# Team12.net
KiCad netlist of a schematic drawn in Altium Designer
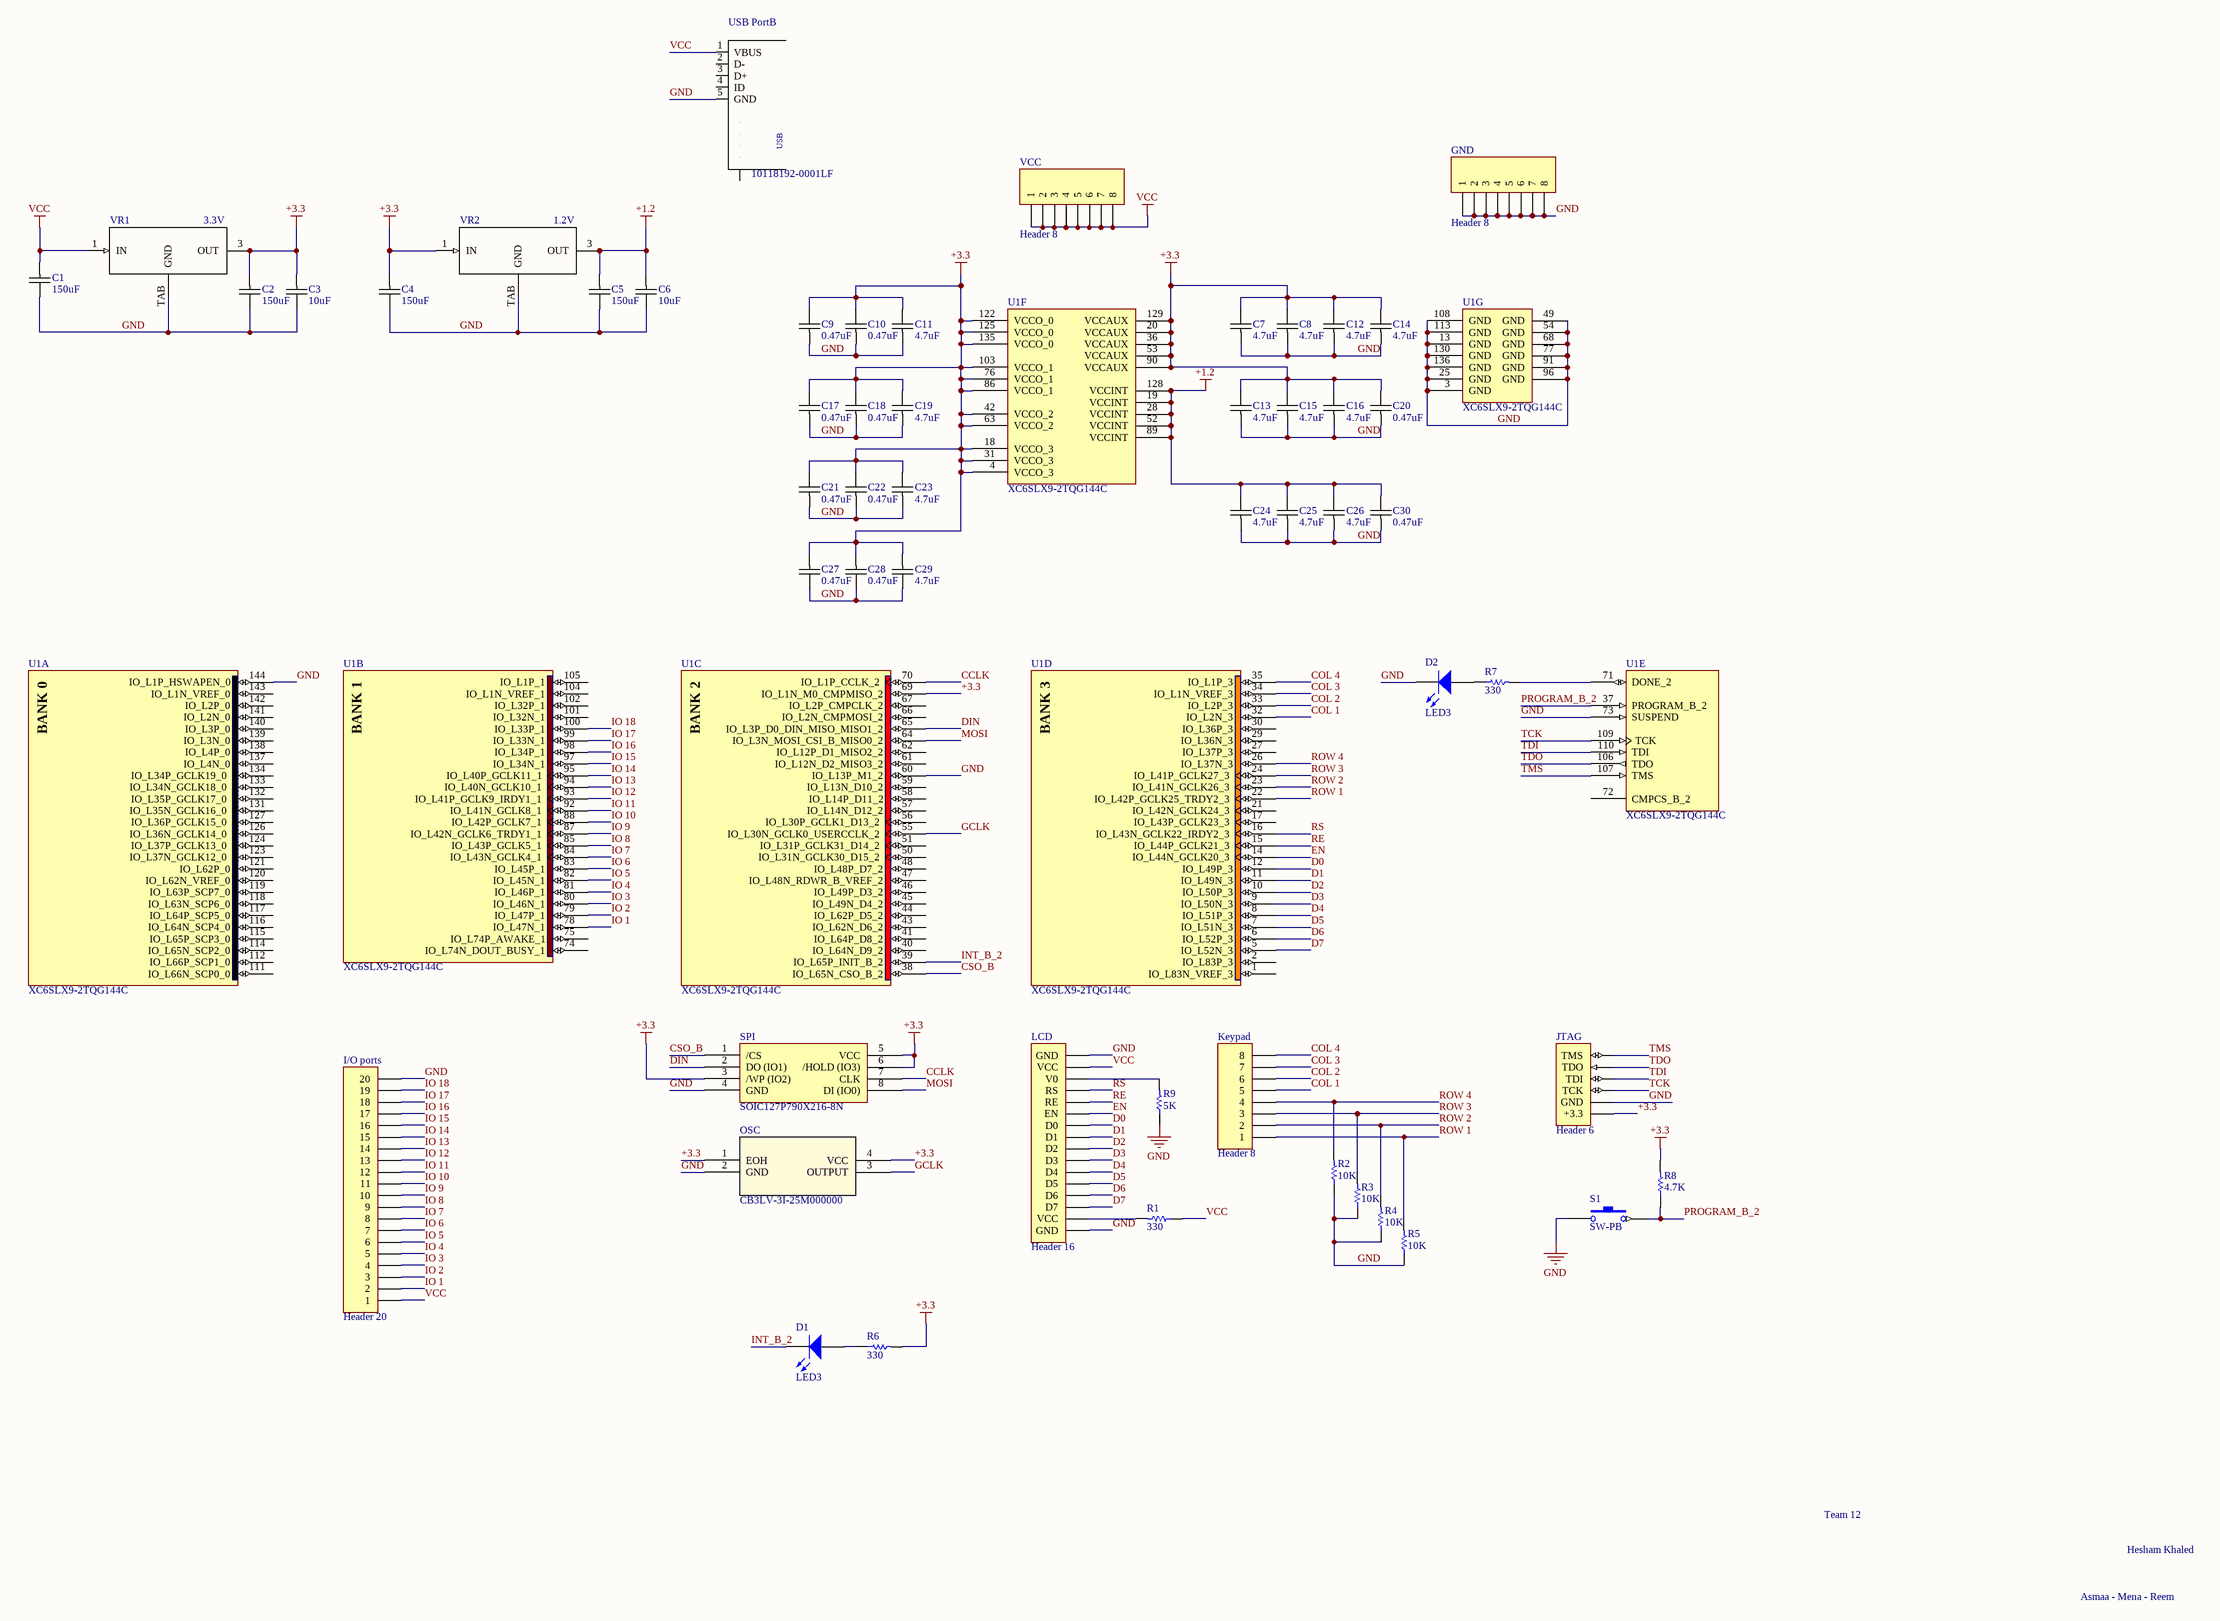
[diagram p0: Team12.SchDoc]

(export (version "E")
  (design (tool "Eeschema 10.0.6"))
  (components
    (comp (ref "C1")
      (value "150uF")
      (footprint "0805C-TBD")
      (description "CAPACITOR 0805 CERAMIC")
      (libsource (lib "vh_altium_library") (part "0805C-27PF-50V-C0G-JOH"))
    )
    (comp (ref "C2")
      (value "150uF")
      (footprint "0805C-TBD")
      (description "CAPACITOR 0805 CERAMIC")
      (libsource (lib "vh_altium_library") (part "0805C-27PF-50V-C0G-JOH"))
    )
    (comp (ref "C3")
      (value "10uF")
      (footprint "0805C-TBD")
      (description "CAPACITOR 0805 CERAMIC")
      (libsource (lib "vh_altium_library") (part "0805C-27PF-50V-C0G-JOH"))
    )
    (comp (ref "C4")
      (value "150uF")
      (footprint "0805C-TBD")
      (description "CAPACITOR 0805 CERAMIC")
      (libsource (lib "vh_altium_library") (part "0805C-27PF-50V-C0G-JOH"))
    )
    (comp (ref "C5")
      (value "150uF")
      (footprint "0805C-TBD")
      (description "CAPACITOR 0805 CERAMIC")
      (libsource (lib "vh_altium_library") (part "0805C-27PF-50V-C0G-JOH"))
    )
    (comp (ref "C6")
      (value "10uF")
      (footprint "0805C-TBD")
      (description "CAPACITOR 0805 CERAMIC")
      (libsource (lib "vh_altium_library") (part "0805C-27PF-50V-C0G-JOH"))
    )
    (comp (ref "C7")
      (value "4.7uF")
      (footprint "0805C-TBD")
      (description "CAPACITOR 0805 CERAMIC")
      (libsource (lib "vh_altium_library") (part "0805C-27PF-50V-C0G-JOH"))
    )
    (comp (ref "C8")
      (value "4.7uF")
      (footprint "0805C-TBD")
      (description "CAPACITOR 0805 CERAMIC")
      (libsource (lib "vh_altium_library") (part "0805C-27PF-50V-C0G-JOH"))
    )
    (comp (ref "C9")
      (value "0.47uF")
      (footprint "0805C-TBD")
      (description "CAPACITOR 0805 CERAMIC")
      (libsource (lib "vh_altium_library") (part "0805C-27PF-50V-C0G-JOH"))
    )
    (comp (ref "C10")
      (value "0.47uF")
      (footprint "0805C-TBD")
      (description "CAPACITOR 0805 CERAMIC")
      (libsource (lib "vh_altium_library") (part "0805C-27PF-50V-C0G-JOH"))
    )
    (comp (ref "C11")
      (value "4.7uF")
      (footprint "0805C-TBD")
      (description "CAPACITOR 0805 CERAMIC")
      (libsource (lib "vh_altium_library") (part "0805C-27PF-50V-C0G-JOH"))
    )
    (comp (ref "C12")
      (value "4.7uF")
      (footprint "0805C-TBD")
      (description "CAPACITOR 0805 CERAMIC")
      (libsource (lib "vh_altium_library") (part "0805C-27PF-50V-C0G-JOH"))
    )
    (comp (ref "C13")
      (value "4.7uF")
      (footprint "0805C-TBD")
      (description "CAPACITOR 0805 CERAMIC")
      (libsource (lib "vh_altium_library") (part "0805C-27PF-50V-C0G-JOH"))
    )
    (comp (ref "C14")
      (value "4.7uF")
      (footprint "0805C-TBD")
      (description "CAPACITOR 0805 CERAMIC")
      (libsource (lib "vh_altium_library") (part "0805C-27PF-50V-C0G-JOH"))
    )
    (comp (ref "C15")
      (value "4.7uF")
      (footprint "0805C-TBD")
      (description "CAPACITOR 0805 CERAMIC")
      (libsource (lib "vh_altium_library") (part "0805C-27PF-50V-C0G-JOH"))
    )
    (comp (ref "C16")
      (value "4.7uF")
      (footprint "0805C-TBD")
      (description "CAPACITOR 0805 CERAMIC")
      (libsource (lib "vh_altium_library") (part "0805C-27PF-50V-C0G-JOH"))
    )
    (comp (ref "C17")
      (value "0.47uF")
      (footprint "0805C-TBD")
      (description "CAPACITOR 0805 CERAMIC")
      (libsource (lib "vh_altium_library") (part "0805C-27PF-50V-C0G-JOH"))
    )
    (comp (ref "C18")
      (value "0.47uF")
      (footprint "0805C-TBD")
      (description "CAPACITOR 0805 CERAMIC")
      (libsource (lib "vh_altium_library") (part "0805C-27PF-50V-C0G-JOH"))
    )
    (comp (ref "C19")
      (value "4.7uF")
      (footprint "0805C-TBD")
      (description "CAPACITOR 0805 CERAMIC")
      (libsource (lib "vh_altium_library") (part "0805C-27PF-50V-C0G-JOH"))
    )
    (comp (ref "C20")
      (value "0.47uF")
      (footprint "0805C-TBD")
      (description "CAPACITOR 0805 CERAMIC")
      (libsource (lib "vh_altium_library") (part "0805C-27PF-50V-C0G-JOH"))
    )
    (comp (ref "C21")
      (value "0.47uF")
      (footprint "0805C-TBD")
      (description "CAPACITOR 0805 CERAMIC")
      (libsource (lib "vh_altium_library") (part "0805C-27PF-50V-C0G-JOH"))
    )
    (comp (ref "C22")
      (value "0.47uF")
      (footprint "0805C-TBD")
      (description "CAPACITOR 0805 CERAMIC")
      (libsource (lib "vh_altium_library") (part "0805C-27PF-50V-C0G-JOH"))
    )
    (comp (ref "C23")
      (value "4.7uF")
      (footprint "0805C-TBD")
      (description "CAPACITOR 0805 CERAMIC")
      (libsource (lib "vh_altium_library") (part "0805C-27PF-50V-C0G-JOH"))
    )
    (comp (ref "C24")
      (value "4.7uF")
      (footprint "0805C-TBD")
      (description "CAPACITOR 0805 CERAMIC")
      (libsource (lib "vh_altium_library") (part "0805C-27PF-50V-C0G-JOH"))
    )
    (comp (ref "C25")
      (value "4.7uF")
      (footprint "0805C-TBD")
      (description "CAPACITOR 0805 CERAMIC")
      (libsource (lib "vh_altium_library") (part "0805C-27PF-50V-C0G-JOH"))
    )
    (comp (ref "C26")
      (value "4.7uF")
      (footprint "0805C-TBD")
      (description "CAPACITOR 0805 CERAMIC")
      (libsource (lib "vh_altium_library") (part "0805C-27PF-50V-C0G-JOH"))
    )
    (comp (ref "C27")
      (value "0.47uF")
      (footprint "0805C-TBD")
      (description "CAPACITOR 0805 CERAMIC")
      (libsource (lib "vh_altium_library") (part "0805C-27PF-50V-C0G-JOH"))
    )
    (comp (ref "C28")
      (value "0.47uF")
      (footprint "0805C-TBD")
      (description "CAPACITOR 0805 CERAMIC")
      (libsource (lib "vh_altium_library") (part "0805C-27PF-50V-C0G-JOH"))
    )
    (comp (ref "C29")
      (value "4.7uF")
      (footprint "0805C-TBD")
      (description "CAPACITOR 0805 CERAMIC")
      (libsource (lib "vh_altium_library") (part "0805C-27PF-50V-C0G-JOH"))
    )
    (comp (ref "C30")
      (value "0.47uF")
      (footprint "0805C-TBD")
      (description "CAPACITOR 0805 CERAMIC")
      (libsource (lib "vh_altium_library") (part "0805C-27PF-50V-C0G-JOH"))
    )
    (comp (ref "D1")
      (value "LED3")
      (footprint "DSO-C2/D5.6")
      (description "Typical BLUE SiC LED")
      (fields (field (name "PUBLISHER") "Altium Limited"))
      (libsource (lib "Miscellaneous Devices") (part "LED3"))
    )
    (comp (ref "D2")
      (value "LED3")
      (footprint "DSO-C2/D5.6")
      (description "Typical BLUE SiC LED")
      (fields (field (name "PUBLISHER") "Altium Limited"))
      (libsource (lib "Miscellaneous Devices") (part "LED3"))
    )
    (comp (ref "GND")
      (value "Header 8")
      (footprint "HDR1X8")
      (description "Header, 8-Pin")
      (fields (field (name "PUBLISHER") "Altium Limited"))
      (libsource (lib "") (part "Header 8_1"))
    )
    (comp (ref "I/O ports")
      (value "Header 20")
      (footprint "HDR1X20")
      (description "Header, 20-Pin")
      (fields (field (name "PUBLISHER") "Altium Limited"))
      (libsource (lib "Miscellaneous Connectors") (part "Header 20"))
    )
    (comp (ref "JTAG")
      (value "Header 6")
      (footprint "HDR1X6")
      (description "Header, 6-Pin")
      (fields (field (name "PUBLISHER") "Altium Limited"))
      (libsource (lib "Miscellaneous Connectors") (part "Header 6"))
    )
    (comp (ref "Keypad")
      (value "Header 8")
      (footprint "HDR1X8")
      (description "Header, 8-Pin")
      (fields (field (name "PUBLISHER") "Altium Limited"))
      (libsource (lib "Miscellaneous Connectors") (part "Header 8"))
    )
    (comp (ref "LCD")
      (value "Header 16")
      (footprint "HDR1X16")
      (description "Header, 16-Pin")
      (fields (field (name "PUBLISHER") "Altium Limited"))
      (libsource (lib "Miscellaneous Connectors") (part "Header 16"))
    )
    (comp (ref "OSC")
      (value "CB3LV-3I-25M000000")
      (footprint "CRYS_CB3LV-3I-01")
      (description "No Description Available")
      (fields
        (field (name "MANUFACTURER_PART_NUMBER") "CB3LV-3I-14M7456")
        (field (name "COPYRIGHT") "Copyright (C) 2018 Accelerated Designs. All rights reserved")
      )
      (libsource (lib "OSC 8MHz CB3LV-3I-25M000000") (part "CB3LV-3I-25M000000"))
    )
    (comp (ref "R1")
      (value "330")
      (footprint "ERA-0805")
      (fields (field (name "PUBLISHER") "Altium Limited"))
      (libsource (lib "Panasonic Resistor") (part "ERA6Y"))
    )
    (comp (ref "R2")
      (value "10K")
      (footprint "ERA-0805")
      (fields (field (name "PUBLISHER") "Altium Limited"))
      (libsource (lib "Panasonic Resistor") (part "ERA6Y"))
    )
    (comp (ref "R3")
      (value "10K")
      (footprint "ERA-0805")
      (fields (field (name "PUBLISHER") "Altium Limited"))
      (libsource (lib "Panasonic Resistor") (part "ERA6Y"))
    )
    (comp (ref "R4")
      (value "10K")
      (footprint "ERA-0805")
      (fields (field (name "PUBLISHER") "Altium Limited"))
      (libsource (lib "Panasonic Resistor") (part "ERA6Y"))
    )
    (comp (ref "R5")
      (value "10K")
      (footprint "ERA-0805")
      (fields (field (name "PUBLISHER") "Altium Limited"))
      (libsource (lib "Panasonic Resistor") (part "ERA6Y"))
    )
    (comp (ref "R6")
      (value "330")
      (footprint "ERA-0805")
      (fields (field (name "PUBLISHER") "Altium Limited"))
      (libsource (lib "Panasonic Resistor") (part "ERA6Y"))
    )
    (comp (ref "R7")
      (value "330")
      (footprint "ERA-0805")
      (fields (field (name "PUBLISHER") "Altium Limited"))
      (libsource (lib "Panasonic Resistor") (part "ERA6Y"))
    )
    (comp (ref "R8")
      (value "4.7K")
      (footprint "ERA-0805")
      (fields (field (name "PUBLISHER") "Altium Limited"))
      (libsource (lib "Panasonic Resistor") (part "ERA6Y"))
    )
    (comp (ref "R9")
      (value "5K")
      (footprint "ERA-0805")
      (fields (field (name "PUBLISHER") "Altium Limited"))
      (libsource (lib "Panasonic Resistor") (part "ERA6Y"))
    )
    (comp (ref "S1")
      (value "SW-PB")
      (footprint "SPST-2")
      (description "Switch")
      (fields (field (name "PUBLISHER") "Altium Limited"))
      (libsource (lib "Miscellaneous Devices") (part "SW-PB"))
    )
    (comp (ref "SPI")
      (value "SOIC127P790X216-8N")
      (footprint "*SOIC127P790X216-8N")
      (description "IC FLASH 8M SPI 104MHZ 8SOIC")
      (libsource (lib "SPI Flash Memory") (part "SOIC127P790X216-8N"))
    )
    (comp (ref "U1")
      (value "XC6SLX9-2TQG144C")
      (footprint "TQG144_N")
      (fields (field (name "PUBLISHER") "Altium Limited"))
      (libsource (lib "Xilinx Spartan-6") (part "XC6SLX9-2TQG144C"))
    )
    (comp (ref "USB PortB")
      (value "10118192-0001LF")
      (footprint "10118192-0001LF_10118192-0001LF(Primary)")
      (description "Conn Micro USB Type B RCP 5 POS 0.65mm Solder RA SMD 5 Terminal 1 Port T/R")
      (fields (field (name "MF") "Amphenol"))
      (libsource (lib "USB Micro Port") (part "10118192-0001LF"))
    )
    (comp (ref "VCC")
      (value "Header 8")
      (footprint "HDR1X8")
      (description "Header, 8-Pin")
      (fields (field (name "PUBLISHER") "Altium Limited"))
      (libsource (lib "") (part "Header 8_1"))
    )
    (comp (ref "VR1")
      (value "3.3V")
      (footprint "*D2PAK_MC7805ACD2TG(Primary)")
      (description "Linear Voltage Regulator IC Positive Fixed 1 Output 1A D2PAK")
      (fields (field (name "MP") "MC7805ACD2TG") (field (name "MF") "ON Semiconductor"))
      (libsource (lib "MC7805ACD2TG") (part "MC7805ACD2TG"))
    )
    (comp (ref "VR2")
      (value "1.2V")
      (footprint "*D2PAK_MC7805ACD2TG(Primary)")
      (description "Linear Voltage Regulator IC Positive Fixed 1 Output 1A D2PAK")
      (fields (field (name "MP") "MC7805ACD2TG") (field (name "MF") "ON Semiconductor"))
      (libsource (lib "MC7805ACD2TG") (part "MC7805ACD2TG"))
    )
  )
  (nets
    (net (code "1") (name "+1.2") (class "Default")
      (node (ref "C24") (pin "2") (pintype "passive"))
      (node (ref "C25") (pin "2") (pintype "passive"))
      (node (ref "C26") (pin "2") (pintype "passive"))
      (node (ref "C30") (pin "2") (pintype "passive"))
      (node (ref "C5") (pin "1") (pintype "passive"))
      (node (ref "C6") (pin "1") (pintype "passive"))
      (node (ref "U1") (pin "128") (pinfunction "VCCINT_128") (pintype "power_in"))
      (node (ref "U1") (pin "19") (pinfunction "VCCINT_19") (pintype "power_in"))
      (node (ref "U1") (pin "28") (pinfunction "VCCINT_28") (pintype "power_in"))
      (node (ref "U1") (pin "52") (pinfunction "VCCINT_52") (pintype "power_in"))
      (node (ref "U1") (pin "89") (pinfunction "VCCINT_89") (pintype "power_in"))
      (node (ref "VR2") (pin "3") (pinfunction "OUT_3") (pintype "power_in"))
    )
    (net (code "2") (name "+3.3") (class "Default")
      (node (ref "C10") (pin "2") (pintype "passive"))
      (node (ref "C11") (pin "2") (pintype "passive"))
      (node (ref "C12") (pin "2") (pintype "passive"))
      (node (ref "C13") (pin "2") (pintype "passive"))
      (node (ref "C14") (pin "2") (pintype "passive"))
      (node (ref "C15") (pin "2") (pintype "passive"))
      (node (ref "C16") (pin "2") (pintype "passive"))
      (node (ref "C17") (pin "2") (pintype "passive"))
      (node (ref "C18") (pin "2") (pintype "passive"))
      (node (ref "C19") (pin "2") (pintype "passive"))
      (node (ref "C2") (pin "1") (pintype "passive"))
      (node (ref "C20") (pin "2") (pintype "passive"))
      (node (ref "C21") (pin "2") (pintype "passive"))
      (node (ref "C22") (pin "2") (pintype "passive"))
      (node (ref "C23") (pin "2") (pintype "passive"))
      (node (ref "C27") (pin "1") (pintype "passive"))
      (node (ref "C28") (pin "1") (pintype "passive"))
      (node (ref "C29") (pin "1") (pintype "passive"))
      (node (ref "C3") (pin "1") (pintype "passive"))
      (node (ref "C4") (pin "1") (pintype "passive"))
      (node (ref "C7") (pin "2") (pintype "passive"))
      (node (ref "C8") (pin "2") (pintype "passive"))
      (node (ref "C9") (pin "2") (pintype "passive"))
      (node (ref "JTAG") (pin "1") (pinfunction "+3.3_1") (pintype "power_in"))
      (node (ref "OSC") (pin "1") (pinfunction "EOH_1") (pintype "passive"))
      (node (ref "OSC") (pin "4") (pinfunction "VCC_4") (pintype "passive"))
      (node (ref "R6") (pin "2") (pinfunction "2_2") (pintype "passive"))
      (node (ref "R8") (pin "2") (pinfunction "2_2") (pintype "passive"))
      (node (ref "SPI") (pin "3") (pinfunction "/WP_(IO2)_3") (pintype "passive"))
      (node (ref "SPI") (pin "5") (pinfunction "VCC_5") (pintype "passive"))
      (node (ref "SPI") (pin "6") (pinfunction "/HOLD_(IO3)_6") (pintype "passive"))
      (node (ref "U1") (pin "103") (pinfunction "VCCO_1_103") (pintype "power_in"))
      (node (ref "U1") (pin "122") (pinfunction "VCCO_0_122") (pintype "power_in"))
      (node (ref "U1") (pin "125") (pinfunction "VCCO_0_125") (pintype "power_in"))
      (node (ref "U1") (pin "129") (pinfunction "VCCAUX_129") (pintype "power_in"))
      (node (ref "U1") (pin "135") (pinfunction "VCCO_0_135") (pintype "power_in"))
      (node (ref "U1") (pin "18") (pinfunction "VCCO_3_18") (pintype "power_in"))
      (node (ref "U1") (pin "20") (pinfunction "VCCAUX_20") (pintype "power_in"))
      (node (ref "U1") (pin "31") (pinfunction "VCCO_3_31") (pintype "power_in"))
      (node (ref "U1") (pin "36") (pinfunction "VCCAUX_36") (pintype "power_in"))
      (node (ref "U1") (pin "4") (pinfunction "VCCO_3_4") (pintype "power_in"))
      (node (ref "U1") (pin "42") (pinfunction "VCCO_2_42") (pintype "power_in"))
      (node (ref "U1") (pin "53") (pinfunction "VCCAUX_53") (pintype "power_in"))
      (node (ref "U1") (pin "63") (pinfunction "VCCO_2_63") (pintype "power_in"))
      (node (ref "U1") (pin "69") (pinfunction "IO_L1N_M0_CMPMISO_2_69") (pintype "bidirectional"))
      (node (ref "U1") (pin "76") (pinfunction "VCCO_1_76") (pintype "power_in"))
      (node (ref "U1") (pin "86") (pinfunction "VCCO_1_86") (pintype "power_in"))
      (node (ref "U1") (pin "90") (pinfunction "VCCAUX_90") (pintype "power_in"))
      (node (ref "VR1") (pin "3") (pinfunction "OUT_3") (pintype "power_in"))
      (node (ref "VR2") (pin "1") (pinfunction "IN_1") (pintype "input"))
    )
    (net (code "3") (name "/CCLK") (class "Default")
      (node (ref "SPI") (pin "7") (pinfunction "CLK_7") (pintype "passive"))
      (node (ref "U1") (pin "70") (pinfunction "IO_L1P_CCLK_2_70") (pintype "bidirectional"))
    )
    (net (code "4") (name "/COL 1") (class "Default")
      (node (ref "Keypad") (pin "5") (pinfunction "5_5") (pintype "passive"))
      (node (ref "U1") (pin "32") (pinfunction "IO_L2N_3_32") (pintype "bidirectional"))
    )
    (net (code "5") (name "/COL 2") (class "Default")
      (node (ref "Keypad") (pin "6") (pinfunction "6_6") (pintype "passive"))
      (node (ref "U1") (pin "33") (pinfunction "IO_L2P_3_33") (pintype "bidirectional"))
    )
    (net (code "6") (name "/COL 3") (class "Default")
      (node (ref "Keypad") (pin "7") (pinfunction "7_7") (pintype "passive"))
      (node (ref "U1") (pin "34") (pinfunction "IO_L1N_VREF_3_34") (pintype "bidirectional"))
    )
    (net (code "7") (name "/COL 4") (class "Default")
      (node (ref "Keypad") (pin "8") (pinfunction "8_8") (pintype "passive"))
      (node (ref "U1") (pin "35") (pinfunction "IO_L1P_3_35") (pintype "bidirectional"))
    )
    (net (code "8") (name "/CSO_B") (class "Default")
      (node (ref "SPI") (pin "1") (pinfunction "/CS_1") (pintype "passive"))
      (node (ref "U1") (pin "38") (pinfunction "IO_L65N_CSO_B_2_38") (pintype "bidirectional"))
    )
    (net (code "9") (name "/D0") (class "Default")
      (node (ref "LCD") (pin "10") (pinfunction "D0_10") (pintype "passive"))
      (node (ref "U1") (pin "12") (pinfunction "IO_L49P_3_12") (pintype "bidirectional"))
    )
    (net (code "10") (name "/D1") (class "Default")
      (node (ref "LCD") (pin "9") (pinfunction "D1_9") (pintype "passive"))
      (node (ref "U1") (pin "11") (pinfunction "IO_L49N_3_11") (pintype "bidirectional"))
    )
    (net (code "11") (name "/D2") (class "Default")
      (node (ref "LCD") (pin "8") (pinfunction "D2_8") (pintype "passive"))
      (node (ref "U1") (pin "10") (pinfunction "IO_L50P_3_10") (pintype "bidirectional"))
    )
    (net (code "12") (name "/D3") (class "Default")
      (node (ref "LCD") (pin "7") (pinfunction "D3_7") (pintype "passive"))
      (node (ref "U1") (pin "9") (pinfunction "IO_L50N_3_9") (pintype "bidirectional"))
    )
    (net (code "13") (name "/D4") (class "Default")
      (node (ref "LCD") (pin "6") (pinfunction "D4_6") (pintype "passive"))
      (node (ref "U1") (pin "8") (pinfunction "IO_L51P_3_8") (pintype "bidirectional"))
    )
    (net (code "14") (name "/D5") (class "Default")
      (node (ref "LCD") (pin "5") (pinfunction "D5_5") (pintype "passive"))
      (node (ref "U1") (pin "7") (pinfunction "IO_L51N_3_7") (pintype "bidirectional"))
    )
    (net (code "15") (name "/D6") (class "Default")
      (node (ref "LCD") (pin "4") (pinfunction "D6_4") (pintype "passive"))
      (node (ref "U1") (pin "6") (pinfunction "IO_L52P_3_6") (pintype "bidirectional"))
    )
    (net (code "16") (name "/D7") (class "Default")
      (node (ref "LCD") (pin "3") (pinfunction "D7_3") (pintype "passive"))
      (node (ref "U1") (pin "5") (pinfunction "IO_L52N_3_5") (pintype "bidirectional"))
    )
    (net (code "17") (name "/DIN") (class "Default")
      (node (ref "SPI") (pin "2") (pinfunction "DO_(IO1)_2") (pintype "passive"))
      (node (ref "U1") (pin "65") (pinfunction "IO_L3P_D0_DIN_MISO_MISO1_2_65") (pintype "bidirectional"))
    )
    (net (code "18") (name "/EN") (class "Default")
      (node (ref "LCD") (pin "11") (pinfunction "EN_11") (pintype "passive"))
      (node (ref "U1") (pin "14") (pinfunction "IO_L44N_GCLK20_3_14") (pintype "bidirectional"))
    )
    (net (code "19") (name "/GCLK") (class "Default")
      (node (ref "OSC") (pin "3") (pinfunction "OUTPUT_3") (pintype "passive"))
      (node (ref "U1") (pin "55") (pinfunction "IO_L30N_GCLK0_USERCCLK_2_55") (pintype "bidirectional"))
    )
    (net (code "20") (name "/INT_B_2") (class "Default")
      (node (ref "D1") (pin "2") (pinfunction "K_2") (pintype "passive"))
      (node (ref "U1") (pin "39") (pinfunction "IO_L65P_INIT_B_2_39") (pintype "bidirectional"))
    )
    (net (code "21") (name "/IO 1") (class "Default")
      (node (ref "I/O ports") (pin "2") (pinfunction "2_2") (pintype "passive"))
      (node (ref "U1") (pin "78") (pinfunction "IO_L47N_1_78") (pintype "bidirectional"))
    )
    (net (code "22") (name "/IO 2") (class "Default")
      (node (ref "I/O ports") (pin "3") (pinfunction "3_3") (pintype "passive"))
      (node (ref "U1") (pin "79") (pinfunction "IO_L47P_1_79") (pintype "bidirectional"))
    )
    (net (code "23") (name "/IO 3") (class "Default")
      (node (ref "I/O ports") (pin "4") (pinfunction "4_4") (pintype "passive"))
      (node (ref "U1") (pin "80") (pinfunction "IO_L46N_1_80") (pintype "bidirectional"))
    )
    (net (code "24") (name "/IO 4") (class "Default")
      (node (ref "I/O ports") (pin "5") (pinfunction "5_5") (pintype "passive"))
      (node (ref "U1") (pin "81") (pinfunction "IO_L46P_1_81") (pintype "bidirectional"))
    )
    (net (code "25") (name "/IO 5") (class "Default")
      (node (ref "I/O ports") (pin "6") (pinfunction "6_6") (pintype "passive"))
      (node (ref "U1") (pin "82") (pinfunction "IO_L45N_1_82") (pintype "bidirectional"))
    )
    (net (code "26") (name "/IO 6") (class "Default")
      (node (ref "I/O ports") (pin "7") (pinfunction "7_7") (pintype "passive"))
      (node (ref "U1") (pin "83") (pinfunction "IO_L45P_1_83") (pintype "bidirectional"))
    )
    (net (code "27") (name "/IO 7") (class "Default")
      (node (ref "I/O ports") (pin "8") (pinfunction "8_8") (pintype "passive"))
      (node (ref "U1") (pin "84") (pinfunction "IO_L43N_GCLK4_1_84") (pintype "bidirectional"))
    )
    (net (code "28") (name "/IO 8") (class "Default")
      (node (ref "I/O ports") (pin "9") (pinfunction "9_9") (pintype "passive"))
      (node (ref "U1") (pin "85") (pinfunction "IO_L43P_GCLK5_1_85") (pintype "bidirectional"))
    )
    (net (code "29") (name "/IO 9") (class "Default")
      (node (ref "I/O ports") (pin "10") (pinfunction "10_10") (pintype "passive"))
      (node (ref "U1") (pin "87") (pinfunction "IO_L42N_GCLK6_TRDY1_1_87") (pintype "bidirectional"))
    )
    (net (code "30") (name "/IO 10") (class "Default")
      (node (ref "I/O ports") (pin "11") (pinfunction "11_11") (pintype "passive"))
      (node (ref "U1") (pin "88") (pinfunction "IO_L42P_GCLK7_1_88") (pintype "bidirectional"))
    )
    (net (code "31") (name "/IO 11") (class "Default")
      (node (ref "I/O ports") (pin "12") (pinfunction "12_12") (pintype "passive"))
      (node (ref "U1") (pin "92") (pinfunction "IO_L41N_GCLK8_1_92") (pintype "bidirectional"))
    )
    (net (code "32") (name "/IO 12") (class "Default")
      (node (ref "I/O ports") (pin "13") (pinfunction "13_13") (pintype "passive"))
      (node (ref "U1") (pin "93") (pinfunction "IO_L41P_GCLK9_IRDY1_1_93") (pintype "bidirectional"))
    )
    (net (code "33") (name "/IO 13") (class "Default")
      (node (ref "I/O ports") (pin "14") (pinfunction "14_14") (pintype "passive"))
      (node (ref "U1") (pin "94") (pinfunction "IO_L40N_GCLK10_1_94") (pintype "bidirectional"))
    )
    (net (code "34") (name "/IO 14") (class "Default")
      (node (ref "I/O ports") (pin "15") (pinfunction "15_15") (pintype "passive"))
      (node (ref "U1") (pin "95") (pinfunction "IO_L40P_GCLK11_1_95") (pintype "bidirectional"))
    )
    (net (code "35") (name "/IO 15") (class "Default")
      (node (ref "I/O ports") (pin "16") (pinfunction "16_16") (pintype "passive"))
      (node (ref "U1") (pin "97") (pinfunction "IO_L34N_1_97") (pintype "bidirectional"))
    )
    (net (code "36") (name "/IO 16") (class "Default")
      (node (ref "I/O ports") (pin "17") (pinfunction "17_17") (pintype "passive"))
      (node (ref "U1") (pin "98") (pinfunction "IO_L34P_1_98") (pintype "bidirectional"))
    )
    (net (code "37") (name "/IO 17") (class "Default")
      (node (ref "I/O ports") (pin "18") (pinfunction "18_18") (pintype "passive"))
      (node (ref "U1") (pin "99") (pinfunction "IO_L33N_1_99") (pintype "bidirectional"))
    )
    (net (code "38") (name "/IO 18") (class "Default")
      (node (ref "I/O ports") (pin "19") (pinfunction "19_19") (pintype "passive"))
      (node (ref "U1") (pin "100") (pinfunction "IO_L33P_1_100") (pintype "bidirectional"))
    )
    (net (code "39") (name "/MOSI") (class "Default")
      (node (ref "SPI") (pin "8") (pinfunction "DI_(IO0)_8") (pintype "passive"))
      (node (ref "U1") (pin "64") (pinfunction "IO_L3N_MOSI_CSI_B_MISO0_2_64") (pintype "bidirectional"))
    )
    (net (code "40") (name "/PROGRAM_B_2") (class "Default")
      (node (ref "R8") (pin "1") (pinfunction "1_1") (pintype "passive"))
      (node (ref "S1") (pin "2") (pinfunction "2_2") (pintype "output"))
      (node (ref "U1") (pin "37") (pinfunction "PROGRAM_B_2_37") (pintype "input"))
    )
    (net (code "41") (name "/RE") (class "Default")
      (node (ref "LCD") (pin "12") (pinfunction "RE_12") (pintype "passive"))
      (node (ref "U1") (pin "15") (pinfunction "IO_L44P_GCLK21_3_15") (pintype "bidirectional"))
    )
    (net (code "42") (name "/ROW 1") (class "Default")
      (node (ref "Keypad") (pin "1") (pinfunction "1_1") (pintype "passive"))
      (node (ref "R5") (pin "2") (pinfunction "2_2") (pintype "passive"))
      (node (ref "U1") (pin "22") (pinfunction "IO_L42P_GCLK25_TRDY2_3_22") (pintype "bidirectional"))
    )
    (net (code "43") (name "/ROW 2") (class "Default")
      (node (ref "Keypad") (pin "2") (pinfunction "2_2") (pintype "passive"))
      (node (ref "R4") (pin "2") (pinfunction "2_2") (pintype "passive"))
      (node (ref "U1") (pin "23") (pinfunction "IO_L41N_GCLK26_3_23") (pintype "bidirectional"))
    )
    (net (code "44") (name "/ROW 3") (class "Default")
      (node (ref "Keypad") (pin "3") (pinfunction "3_3") (pintype "passive"))
      (node (ref "R3") (pin "2") (pinfunction "2_2") (pintype "passive"))
      (node (ref "U1") (pin "24") (pinfunction "IO_L41P_GCLK27_3_24") (pintype "bidirectional"))
    )
    (net (code "45") (name "/ROW 4") (class "Default")
      (node (ref "Keypad") (pin "4") (pinfunction "4_4") (pintype "passive"))
      (node (ref "R2") (pin "2") (pinfunction "2_2") (pintype "passive"))
      (node (ref "U1") (pin "26") (pinfunction "IO_L37N_3_26") (pintype "bidirectional"))
    )
    (net (code "46") (name "/RS") (class "Default")
      (node (ref "LCD") (pin "13") (pinfunction "RS_13") (pintype "passive"))
      (node (ref "U1") (pin "16") (pinfunction "IO_L43N_GCLK22_IRDY2_3_16") (pintype "bidirectional"))
    )
    (net (code "47") (name "/TCK") (class "Default")
      (node (ref "JTAG") (pin "3") (pinfunction "TCK_3") (pintype "bidirectional"))
      (node (ref "U1") (pin "109") (pinfunction "TCK_109") (pintype "input"))
    )
    (net (code "48") (name "/TDI") (class "Default")
      (node (ref "JTAG") (pin "4") (pinfunction "TDI_4") (pintype "bidirectional"))
      (node (ref "U1") (pin "110") (pinfunction "TDI_110") (pintype "input"))
    )
    (net (code "49") (name "/TDO") (class "Default")
      (node (ref "JTAG") (pin "5") (pinfunction "TDO_5") (pintype "input"))
      (node (ref "U1") (pin "106") (pinfunction "TDO_106") (pintype "output"))
    )
    (net (code "50") (name "/TMS") (class "Default")
      (node (ref "JTAG") (pin "6") (pinfunction "TMS_6") (pintype "bidirectional"))
      (node (ref "U1") (pin "107") (pinfunction "TMS_107") (pintype "input"))
    )
    (net (code "51") (name "GND") (class "Default")
      (node (ref "C1") (pin "2") (pintype "passive"))
      (node (ref "C10") (pin "1") (pintype "passive"))
      (node (ref "C11") (pin "1") (pintype "passive"))
      (node (ref "C12") (pin "1") (pintype "passive"))
      (node (ref "C13") (pin "1") (pintype "passive"))
      (node (ref "C14") (pin "1") (pintype "passive"))
      (node (ref "C15") (pin "1") (pintype "passive"))
      (node (ref "C16") (pin "1") (pintype "passive"))
      (node (ref "C17") (pin "1") (pintype "passive"))
      (node (ref "C18") (pin "1") (pintype "passive"))
      (node (ref "C19") (pin "1") (pintype "passive"))
      (node (ref "C2") (pin "2") (pintype "passive"))
      (node (ref "C20") (pin "1") (pintype "passive"))
      (node (ref "C21") (pin "1") (pintype "passive"))
      (node (ref "C22") (pin "1") (pintype "passive"))
      (node (ref "C23") (pin "1") (pintype "passive"))
      (node (ref "C24") (pin "1") (pintype "passive"))
      (node (ref "C25") (pin "1") (pintype "passive"))
      (node (ref "C26") (pin "1") (pintype "passive"))
      (node (ref "C27") (pin "2") (pintype "passive"))
      (node (ref "C28") (pin "2") (pintype "passive"))
      (node (ref "C29") (pin "2") (pintype "passive"))
      (node (ref "C3") (pin "2") (pintype "passive"))
      (node (ref "C30") (pin "1") (pintype "passive"))
      (node (ref "C4") (pin "2") (pintype "passive"))
      (node (ref "C5") (pin "2") (pintype "passive"))
      (node (ref "C6") (pin "2") (pintype "passive"))
      (node (ref "C7") (pin "1") (pintype "passive"))
      (node (ref "C8") (pin "1") (pintype "passive"))
      (node (ref "C9") (pin "1") (pintype "passive"))
      (node (ref "D2") (pin "2") (pinfunction "K_2") (pintype "passive"))
      (node (ref "GND") (pin "1") (pinfunction "1_1") (pintype "passive"))
      (node (ref "GND") (pin "2") (pinfunction "2_2") (pintype "passive"))
      (node (ref "GND") (pin "3") (pinfunction "3_3") (pintype "passive"))
      (node (ref "GND") (pin "4") (pinfunction "4_4") (pintype "passive"))
      (node (ref "GND") (pin "5") (pinfunction "5_5") (pintype "passive"))
      (node (ref "GND") (pin "6") (pinfunction "6_6") (pintype "passive"))
      (node (ref "GND") (pin "7") (pinfunction "7_7") (pintype "passive"))
      (node (ref "GND") (pin "8") (pinfunction "8_8") (pintype "passive"))
      (node (ref "I/O ports") (pin "20") (pinfunction "20_20") (pintype "passive"))
      (node (ref "JTAG") (pin "2") (pinfunction "GND_2") (pintype "power_in"))
      (node (ref "LCD") (pin "1") (pinfunction "GND_1") (pintype "power_in"))
      (node (ref "LCD") (pin "16") (pinfunction "GND_16") (pintype "power_in"))
      (node (ref "OSC") (pin "2") (pinfunction "GND_2") (pintype "passive"))
      (node (ref "R2") (pin "1") (pinfunction "1_1") (pintype "passive"))
      (node (ref "R3") (pin "1") (pinfunction "1_1") (pintype "passive"))
      (node (ref "R4") (pin "1") (pinfunction "1_1") (pintype "passive"))
      (node (ref "R5") (pin "1") (pinfunction "1_1") (pintype "passive"))
      (node (ref "R9") (pin "1") (pinfunction "1_1") (pintype "passive"))
      (node (ref "S1") (pin "1") (pinfunction "GND_1") (pintype "power_in"))
      (node (ref "SPI") (pin "4") (pinfunction "GND_4") (pintype "passive"))
      (node (ref "U1") (pin "108") (pinfunction "GND_108") (pintype "power_in"))
      (node (ref "U1") (pin "113") (pinfunction "GND_113") (pintype "power_in"))
      (node (ref "U1") (pin "13") (pinfunction "GND_13") (pintype "power_in"))
      (node (ref "U1") (pin "130") (pinfunction "GND_130") (pintype "power_in"))
      (node (ref "U1") (pin "136") (pinfunction "GND_136") (pintype "power_in"))
      (node (ref "U1") (pin "144") (pinfunction "IO_L1P_HSWAPEN_0_144") (pintype "bidirectional"))
      (node (ref "U1") (pin "25") (pinfunction "GND_25") (pintype "power_in"))
      (node (ref "U1") (pin "3") (pinfunction "GND_3") (pintype "power_in"))
      (node (ref "U1") (pin "49") (pinfunction "GND_49") (pintype "power_in"))
      (node (ref "U1") (pin "54") (pinfunction "GND_54") (pintype "power_in"))
      (node (ref "U1") (pin "60") (pinfunction "IO_L13P_M1_2_60") (pintype "bidirectional"))
      (node (ref "U1") (pin "68") (pinfunction "GND_68") (pintype "power_in"))
      (node (ref "U1") (pin "73") (pinfunction "SUSPEND_73") (pintype "input"))
      (node (ref "U1") (pin "77") (pinfunction "GND_77") (pintype "power_in"))
      (node (ref "U1") (pin "91") (pinfunction "GND_91") (pintype "power_in"))
      (node (ref "U1") (pin "96") (pinfunction "GND_96") (pintype "power_in"))
      (node (ref "USB PortB") (pin "5") (pinfunction "GND_5") (pintype "power_in"))
      (node (ref "VR1") (pin "TAB") (pinfunction "GND_TAB") (pintype "power_in"))
      (node (ref "VR2") (pin "TAB") (pinfunction "GND_TAB") (pintype "power_in"))
    )
    (net (code "52") (name "Net-(D1-A)") (class "Default")
      (node (ref "D1") (pin "1") (pinfunction "A_1") (pintype "passive"))
      (node (ref "R6") (pin "1") (pinfunction "1_1") (pintype "passive"))
    )
    (net (code "53") (name "Net-(D2-A)") (class "Default")
      (node (ref "D2") (pin "1") (pinfunction "A_1") (pintype "passive"))
      (node (ref "R7") (pin "1") (pinfunction "1_1") (pintype "passive"))
    )
    (net (code "54") (name "Net-(LCD-V0)") (class "Default")
      (node (ref "LCD") (pin "14") (pinfunction "V0_14") (pintype "passive"))
      (node (ref "R9") (pin "2") (pinfunction "2_2") (pintype "passive"))
    )
    (net (code "55") (name "Net-(LCD-VCC-Pad2)") (class "Default")
      (node (ref "LCD") (pin "2") (pinfunction "VCC_2") (pintype "power_in"))
      (node (ref "R1") (pin "2") (pinfunction "2_2") (pintype "passive"))
    )
    (net (code "56") (name "Net-(U1E-DONE_2)") (class "Default")
      (node (ref "R7") (pin "2") (pinfunction "2_2") (pintype "passive"))
      (node (ref "U1") (pin "71") (pinfunction "DONE_2_71") (pintype "bidirectional"))
    )
    (net (code "57") (name "VCC") (class "Default")
      (node (ref "C1") (pin "1") (pintype "passive"))
      (node (ref "I/O ports") (pin "1") (pinfunction "1_1") (pintype "passive"))
      (node (ref "LCD") (pin "15") (pinfunction "VCC_15") (pintype "power_in"))
      (node (ref "R1") (pin "1") (pinfunction "1_1") (pintype "passive"))
      (node (ref "USB PortB") (pin "1") (pinfunction "VBUS_1") (pintype "power_in"))
      (node (ref "VCC") (pin "1") (pinfunction "1_1") (pintype "passive"))
      (node (ref "VCC") (pin "2") (pinfunction "2_2") (pintype "passive"))
      (node (ref "VCC") (pin "3") (pinfunction "3_3") (pintype "passive"))
      (node (ref "VCC") (pin "4") (pinfunction "4_4") (pintype "passive"))
      (node (ref "VCC") (pin "5") (pinfunction "5_5") (pintype "passive"))
      (node (ref "VCC") (pin "6") (pinfunction "6_6") (pintype "passive"))
      (node (ref "VCC") (pin "7") (pinfunction "7_7") (pintype "passive"))
      (node (ref "VCC") (pin "8") (pinfunction "8_8") (pintype "passive"))
      (node (ref "VR1") (pin "1") (pinfunction "IN_1") (pintype "input"))
    )
    (net (code "58") (name "unconnected-(U1A-IO_L1N_VREF_0-Pad143)") (class "Default")
      (node (ref "U1") (pin "143") (pinfunction "IO_L1N_VREF_0_143") (pintype "bidirectional"))
    )
    (net (code "59") (name "unconnected-(U1A-IO_L2N_0-Pad141)") (class "Default")
      (node (ref "U1") (pin "141") (pinfunction "IO_L2N_0_141") (pintype "bidirectional"))
    )
    (net (code "60") (name "unconnected-(U1A-IO_L2P_0-Pad142)") (class "Default")
      (node (ref "U1") (pin "142") (pinfunction "IO_L2P_0_142") (pintype "bidirectional"))
    )
    (net (code "61") (name "unconnected-(U1A-IO_L3N_0-Pad139)") (class "Default")
      (node (ref "U1") (pin "139") (pinfunction "IO_L3N_0_139") (pintype "bidirectional"))
    )
    (net (code "62") (name "unconnected-(U1A-IO_L3P_0-Pad140)") (class "Default")
      (node (ref "U1") (pin "140") (pinfunction "IO_L3P_0_140") (pintype "bidirectional"))
    )
    (net (code "63") (name "unconnected-(U1A-IO_L4N_0-Pad137)") (class "Default")
      (node (ref "U1") (pin "137") (pinfunction "IO_L4N_0_137") (pintype "bidirectional"))
    )
    (net (code "64") (name "unconnected-(U1A-IO_L4P_0-Pad138)") (class "Default")
      (node (ref "U1") (pin "138") (pinfunction "IO_L4P_0_138") (pintype "bidirectional"))
    )
    (net (code "65") (name "unconnected-(U1A-IO_L34N_GCLK18_0-Pad133)") (class "Default")
      (node (ref "U1") (pin "133") (pinfunction "IO_L34N_GCLK18_0_133") (pintype "bidirectional"))
    )
    (net (code "66") (name "unconnected-(U1A-IO_L34P_GCLK19_0-Pad134)") (class "Default")
      (node (ref "U1") (pin "134") (pinfunction "IO_L34P_GCLK19_0_134") (pintype "bidirectional"))
    )
    (net (code "67") (name "unconnected-(U1A-IO_L35N_GCLK16_0-Pad131)") (class "Default")
      (node (ref "U1") (pin "131") (pinfunction "IO_L35N_GCLK16_0_131") (pintype "bidirectional"))
    )
    (net (code "68") (name "unconnected-(U1A-IO_L35P_GCLK17_0-Pad132)") (class "Default")
      (node (ref "U1") (pin "132") (pinfunction "IO_L35P_GCLK17_0_132") (pintype "bidirectional"))
    )
    (net (code "69") (name "unconnected-(U1A-IO_L36N_GCLK14_0-Pad126)") (class "Default")
      (node (ref "U1") (pin "126") (pinfunction "IO_L36N_GCLK14_0_126") (pintype "bidirectional"))
    )
    (net (code "70") (name "unconnected-(U1A-IO_L36P_GCLK15_0-Pad127)") (class "Default")
      (node (ref "U1") (pin "127") (pinfunction "IO_L36P_GCLK15_0_127") (pintype "bidirectional"))
    )
    (net (code "71") (name "unconnected-(U1A-IO_L37N_GCLK12_0-Pad123)") (class "Default")
      (node (ref "U1") (pin "123") (pinfunction "IO_L37N_GCLK12_0_123") (pintype "bidirectional"))
    )
    (net (code "72") (name "unconnected-(U1A-IO_L37P_GCLK13_0-Pad124)") (class "Default")
      (node (ref "U1") (pin "124") (pinfunction "IO_L37P_GCLK13_0_124") (pintype "bidirectional"))
    )
    (net (code "73") (name "unconnected-(U1A-IO_L62N_VREF_0-Pad120)") (class "Default")
      (node (ref "U1") (pin "120") (pinfunction "IO_L62N_VREF_0_120") (pintype "bidirectional"))
    )
    (net (code "74") (name "unconnected-(U1A-IO_L62P_0-Pad121)") (class "Default")
      (node (ref "U1") (pin "121") (pinfunction "IO_L62P_0_121") (pintype "bidirectional"))
    )
    (net (code "75") (name "unconnected-(U1A-IO_L63N_SCP6_0-Pad118)") (class "Default")
      (node (ref "U1") (pin "118") (pinfunction "IO_L63N_SCP6_0_118") (pintype "bidirectional"))
    )
    (net (code "76") (name "unconnected-(U1A-IO_L63P_SCP7_0-Pad119)") (class "Default")
      (node (ref "U1") (pin "119") (pinfunction "IO_L63P_SCP7_0_119") (pintype "bidirectional"))
    )
    (net (code "77") (name "unconnected-(U1A-IO_L64N_SCP4_0-Pad116)") (class "Default")
      (node (ref "U1") (pin "116") (pinfunction "IO_L64N_SCP4_0_116") (pintype "bidirectional"))
    )
    (net (code "78") (name "unconnected-(U1A-IO_L64P_SCP5_0-Pad117)") (class "Default")
      (node (ref "U1") (pin "117") (pinfunction "IO_L64P_SCP5_0_117") (pintype "bidirectional"))
    )
    (net (code "79") (name "unconnected-(U1A-IO_L65N_SCP2_0-Pad114)") (class "Default")
      (node (ref "U1") (pin "114") (pinfunction "IO_L65N_SCP2_0_114") (pintype "bidirectional"))
    )
    (net (code "80") (name "unconnected-(U1A-IO_L65P_SCP3_0-Pad115)") (class "Default")
      (node (ref "U1") (pin "115") (pinfunction "IO_L65P_SCP3_0_115") (pintype "bidirectional"))
    )
    (net (code "81") (name "unconnected-(U1A-IO_L66N_SCP0_0-Pad111)") (class "Default")
      (node (ref "U1") (pin "111") (pinfunction "IO_L66N_SCP0_0_111") (pintype "bidirectional"))
    )
    (net (code "82") (name "unconnected-(U1A-IO_L66P_SCP1_0-Pad112)") (class "Default")
      (node (ref "U1") (pin "112") (pinfunction "IO_L66P_SCP1_0_112") (pintype "bidirectional"))
    )
    (net (code "83") (name "unconnected-(U1B-IO_L1N_VREF_1-Pad104)") (class "Default")
      (node (ref "U1") (pin "104") (pinfunction "IO_L1N_VREF_1_104") (pintype "bidirectional"))
    )
    (net (code "84") (name "unconnected-(U1B-IO_L1P_1-Pad105)") (class "Default")
      (node (ref "U1") (pin "105") (pinfunction "IO_L1P_1_105") (pintype "bidirectional"))
    )
    (net (code "85") (name "unconnected-(U1B-IO_L32N_1-Pad101)") (class "Default")
      (node (ref "U1") (pin "101") (pinfunction "IO_L32N_1_101") (pintype "bidirectional"))
    )
    (net (code "86") (name "unconnected-(U1B-IO_L32P_1-Pad102)") (class "Default")
      (node (ref "U1") (pin "102") (pinfunction "IO_L32P_1_102") (pintype "bidirectional"))
    )
    (net (code "87") (name "unconnected-(U1B-IO_L74N_DOUT_BUSY_1-Pad74)") (class "Default")
      (node (ref "U1") (pin "74") (pinfunction "IO_L74N_DOUT_BUSY_1_74") (pintype "bidirectional"))
    )
    (net (code "88") (name "unconnected-(U1B-IO_L74P_AWAKE_1-Pad75)") (class "Default")
      (node (ref "U1") (pin "75") (pinfunction "IO_L74P_AWAKE_1_75") (pintype "bidirectional"))
    )
    (net (code "89") (name "unconnected-(U1C-IO_L2N_CMPMOSI_2-Pad66)") (class "Default")
      (node (ref "U1") (pin "66") (pinfunction "IO_L2N_CMPMOSI_2_66") (pintype "bidirectional"))
    )
    (net (code "90") (name "unconnected-(U1C-IO_L2P_CMPCLK_2-Pad67)") (class "Default")
      (node (ref "U1") (pin "67") (pinfunction "IO_L2P_CMPCLK_2_67") (pintype "bidirectional"))
    )
    (net (code "91") (name "unconnected-(U1C-IO_L12N_D2_MISO3_2-Pad61)") (class "Default")
      (node (ref "U1") (pin "61") (pinfunction "IO_L12N_D2_MISO3_2_61") (pintype "bidirectional"))
    )
    (net (code "92") (name "unconnected-(U1C-IO_L12P_D1_MISO2_2-Pad62)") (class "Default")
      (node (ref "U1") (pin "62") (pinfunction "IO_L12P_D1_MISO2_2_62") (pintype "bidirectional"))
    )
    (net (code "93") (name "unconnected-(U1C-IO_L13N_D10_2-Pad59)") (class "Default")
      (node (ref "U1") (pin "59") (pinfunction "IO_L13N_D10_2_59") (pintype "bidirectional"))
    )
    (net (code "94") (name "unconnected-(U1C-IO_L14N_D12_2-Pad57)") (class "Default")
      (node (ref "U1") (pin "57") (pinfunction "IO_L14N_D12_2_57") (pintype "bidirectional"))
    )
    (net (code "95") (name "unconnected-(U1C-IO_L14P_D11_2-Pad58)") (class "Default")
      (node (ref "U1") (pin "58") (pinfunction "IO_L14P_D11_2_58") (pintype "bidirectional"))
    )
    (net (code "96") (name "unconnected-(U1C-IO_L30P_GCLK1_D13_2-Pad56)") (class "Default")
      (node (ref "U1") (pin "56") (pinfunction "IO_L30P_GCLK1_D13_2_56") (pintype "bidirectional"))
    )
    (net (code "97") (name "unconnected-(U1C-IO_L31N_GCLK30_D15_2-Pad50)") (class "Default")
      (node (ref "U1") (pin "50") (pinfunction "IO_L31N_GCLK30_D15_2_50") (pintype "bidirectional"))
    )
    (net (code "98") (name "unconnected-(U1C-IO_L31P_GCLK31_D14_2-Pad51)") (class "Default")
      (node (ref "U1") (pin "51") (pinfunction "IO_L31P_GCLK31_D14_2_51") (pintype "bidirectional"))
    )
    (net (code "99") (name "unconnected-(U1C-IO_L48N_RDWR_B_VREF_2-Pad47)") (class "Default")
      (node (ref "U1") (pin "47") (pinfunction "IO_L48N_RDWR_B_VREF_2_47") (pintype "bidirectional"))
    )
    (net (code "100") (name "unconnected-(U1C-IO_L48P_D7_2-Pad48)") (class "Default")
      (node (ref "U1") (pin "48") (pinfunction "IO_L48P_D7_2_48") (pintype "bidirectional"))
    )
    (net (code "101") (name "unconnected-(U1C-IO_L49N_D4_2-Pad45)") (class "Default")
      (node (ref "U1") (pin "45") (pinfunction "IO_L49N_D4_2_45") (pintype "bidirectional"))
    )
    (net (code "102") (name "unconnected-(U1C-IO_L49P_D3_2-Pad46)") (class "Default")
      (node (ref "U1") (pin "46") (pinfunction "IO_L49P_D3_2_46") (pintype "bidirectional"))
    )
    (net (code "103") (name "unconnected-(U1C-IO_L62N_D6_2-Pad43)") (class "Default")
      (node (ref "U1") (pin "43") (pinfunction "IO_L62N_D6_2_43") (pintype "bidirectional"))
    )
    (net (code "104") (name "unconnected-(U1C-IO_L62P_D5_2-Pad44)") (class "Default")
      (node (ref "U1") (pin "44") (pinfunction "IO_L62P_D5_2_44") (pintype "bidirectional"))
    )
    (net (code "105") (name "unconnected-(U1C-IO_L64N_D9_2-Pad40)") (class "Default")
      (node (ref "U1") (pin "40") (pinfunction "IO_L64N_D9_2_40") (pintype "bidirectional"))
    )
    (net (code "106") (name "unconnected-(U1C-IO_L64P_D8_2-Pad41)") (class "Default")
      (node (ref "U1") (pin "41") (pinfunction "IO_L64P_D8_2_41") (pintype "bidirectional"))
    )
    (net (code "107") (name "unconnected-(U1D-IO_L36N_3-Pad29)") (class "Default")
      (node (ref "U1") (pin "29") (pinfunction "IO_L36N_3_29") (pintype "bidirectional"))
    )
    (net (code "108") (name "unconnected-(U1D-IO_L36P_3-Pad30)") (class "Default")
      (node (ref "U1") (pin "30") (pinfunction "IO_L36P_3_30") (pintype "bidirectional"))
    )
    (net (code "109") (name "unconnected-(U1D-IO_L37P_3-Pad27)") (class "Default")
      (node (ref "U1") (pin "27") (pinfunction "IO_L37P_3_27") (pintype "bidirectional"))
    )
    (net (code "110") (name "unconnected-(U1D-IO_L42N_GCLK24_3-Pad21)") (class "Default")
      (node (ref "U1") (pin "21") (pinfunction "IO_L42N_GCLK24_3_21") (pintype "bidirectional"))
    )
    (net (code "111") (name "unconnected-(U1D-IO_L43P_GCLK23_3-Pad17)") (class "Default")
      (node (ref "U1") (pin "17") (pinfunction "IO_L43P_GCLK23_3_17") (pintype "bidirectional"))
    )
    (net (code "112") (name "unconnected-(U1D-IO_L83N_VREF_3-Pad1)") (class "Default")
      (node (ref "U1") (pin "1") (pinfunction "IO_L83N_VREF_3_1") (pintype "bidirectional"))
    )
    (net (code "113") (name "unconnected-(U1D-IO_L83P_3-Pad2)") (class "Default")
      (node (ref "U1") (pin "2") (pinfunction "IO_L83P_3_2") (pintype "bidirectional"))
    )
    (net (code "114") (name "unconnected-(U1E-CMPCS_B_2-Pad72)") (class "Default")
      (node (ref "U1") (pin "72") (pinfunction "CMPCS_B_2_72") (pintype "input"))
    )
    (net (code "115") (name "unconnected-(USB PortB-D+-Pad3)") (class "Default")
      (node (ref "USB PortB") (pin "3") (pinfunction "D+_3") (pintype "passive"))
    )
    (net (code "116") (name "unconnected-(USB PortB-D--Pad2)") (class "Default")
      (node (ref "USB PortB") (pin "2") (pinfunction "D-_2") (pintype "passive"))
    )
    (net (code "117") (name "unconnected-(USB PortB-ID-Pad4)") (class "Default")
      (node (ref "USB PortB") (pin "4") (pinfunction "ID_4") (pintype "passive"))
    )
    (net (code "118") (name "unconnected-(USB PortB-S-PadM1)") (class "Default")
      (node (ref "USB PortB") (pin "M1") (pinfunction "S_M1") (pintype "passive"))
    )
    (net (code "119") (name "unconnected-(USB PortB-S-PadM2)") (class "Default")
      (node (ref "USB PortB") (pin "M2") (pinfunction "S_M2") (pintype "passive"))
    )
    (net (code "120") (name "unconnected-(USB PortB-S-PadS1)") (class "Default")
      (node (ref "USB PortB") (pin "S1") (pinfunction "S_S1") (pintype "passive"))
    )
    (net (code "121") (name "unconnected-(USB PortB-S-PadS2)") (class "Default")
      (node (ref "USB PortB") (pin "S2") (pinfunction "S_S2") (pintype "passive"))
    )
    (net (code "122") (name "unconnected-(USB PortB-S-PadS3)") (class "Default")
      (node (ref "USB PortB") (pin "S3") (pinfunction "S_S3") (pintype "passive"))
    )
    (net (code "123") (name "unconnected-(USB PortB-S-PadS4)") (class "Default")
      (node (ref "USB PortB") (pin "S4") (pinfunction "S_S4") (pintype "passive"))
    )
  )
)
